# oscillator-v2.net
KiCad netlist of a schematic drawn in EAGLE
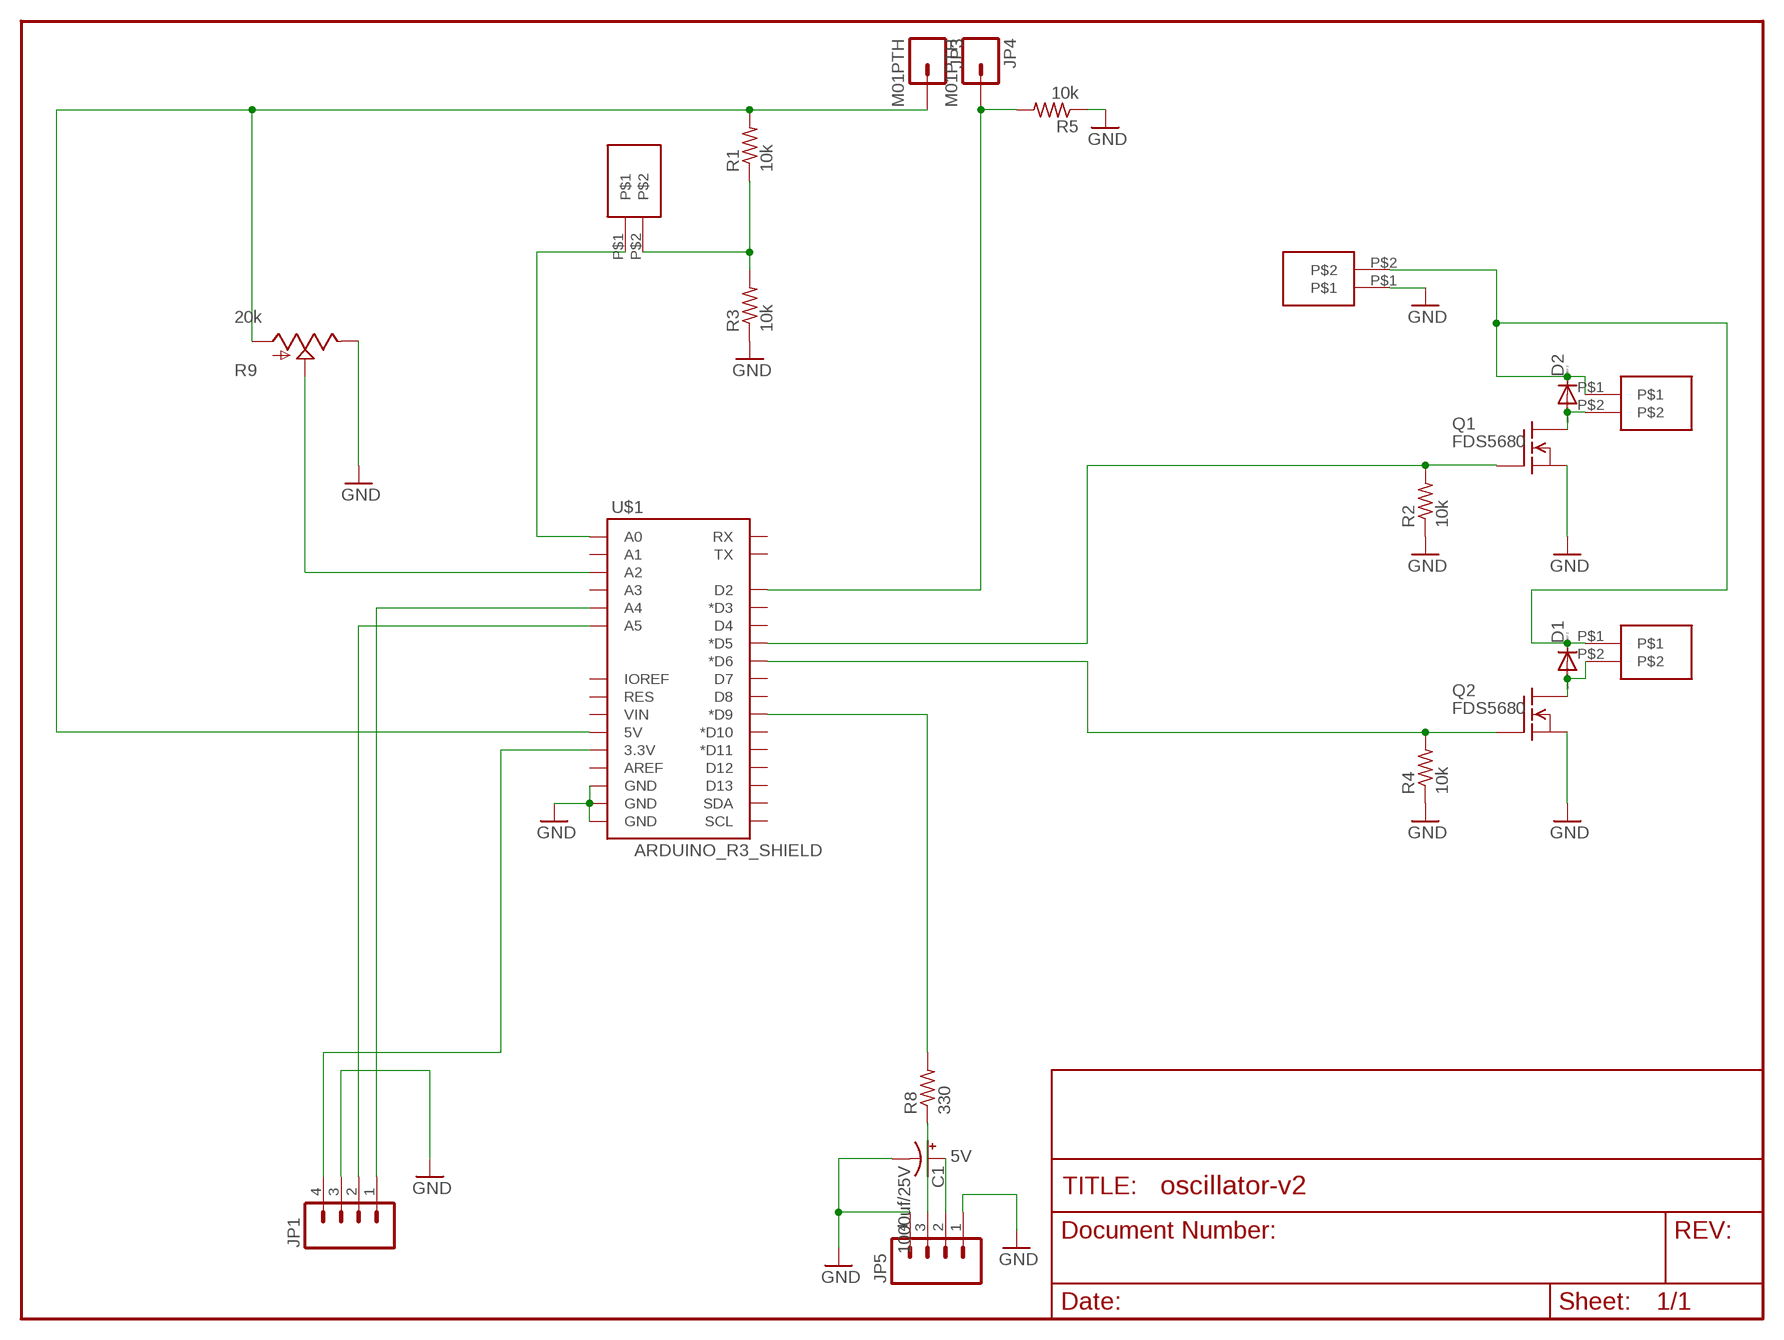
[diagram p0: schematic, sheet 1]

(export (version "E")
  (design (tool "Eeschema 10.0.6"))
  (components
    (comp (ref "C1")
      (value "1000uf/25V")
      (footprint "eagle-import:CPOL-RADIAL-1000UF-25V-KIT")
      (libsource (lib "eagle-import") (part "1000UF-25V(PTH)KIT"))
    )
    (comp (ref "D1")
      (value "DIODE-DO-214AC")
      (footprint "eagle-import:DO-214AC")
      (libsource (lib "eagle-import") (part "DIODE-DO-214AC"))
    )
    (comp (ref "D2")
      (value "DIODE-DO-214AC")
      (footprint "eagle-import:DO-214AC")
      (libsource (lib "eagle-import") (part "DIODE-DO-214AC"))
    )
    (comp (ref "JP1")
      (value "M04PTH")
      (footprint "eagle-import:1X04")
      (libsource (lib "eagle-import") (part "M04PTH"))
    )
    (comp (ref "JP3")
      (value "M01PTH")
      (footprint "eagle-import:1X01")
      (libsource (lib "eagle-import") (part "M01PTH"))
    )
    (comp (ref "JP4")
      (value "M01PTH")
      (footprint "eagle-import:1X01")
      (libsource (lib "eagle-import") (part "M01PTH"))
    )
    (comp (ref "JP5")
      (value "M04PTH")
      (footprint "eagle-import:1X04")
      (libsource (lib "eagle-import") (part "M04PTH"))
    )
    (comp (ref "Q1")
      (value "FDS5680")
      (footprint "eagle-import:SO-8")
      (libsource (lib "eagle-import") (part "FDS5680"))
    )
    (comp (ref "Q2")
      (value "FDS5680")
      (footprint "eagle-import:SO-8")
      (libsource (lib "eagle-import") (part "FDS5680"))
    )
    (comp (ref "R1")
      (value "10k")
      (footprint "eagle-import:R0603")
      (libsource (lib "eagle-import") (part "R-US_R0603"))
    )
    (comp (ref "R2")
      (value "10k")
      (footprint "eagle-import:R0603")
      (libsource (lib "eagle-import") (part "R-US_R0603"))
    )
    (comp (ref "R3")
      (value "10k")
      (footprint "eagle-import:R0603")
      (libsource (lib "eagle-import") (part "R-US_R0603"))
    )
    (comp (ref "R4")
      (value "10k")
      (footprint "eagle-import:R0603")
      (libsource (lib "eagle-import") (part "R-US_R0603"))
    )
    (comp (ref "R5")
      (value "10k")
      (footprint "eagle-import:R0603")
      (libsource (lib "eagle-import") (part "R-US_R0603"))
    )
    (comp (ref "R8")
      (value "330")
      (footprint "eagle-import:R0603")
      (libsource (lib "eagle-import") (part "R-US_R0603"))
    )
    (comp (ref "R9")
      (value "20k")
      (footprint "eagle-import:ALPS_POT_KIT")
      (libsource (lib "eagle-import") (part "POTALPS-KIT"))
    )
    (comp (ref "U$1")
      (value "ARDUINO_R3_SHIELD")
      (footprint "eagle-import:UNO_R3_SHIELD")
      (libsource (lib "eagle-import") (part "ARDUINO_R3_SHIELD"))
    )
    (comp (ref "U$6")
      (value "SPRING-TERMINAL")
      (footprint "eagle-import:SPRING-TERMINAL")
      (libsource (lib "eagle-import") (part "SPRING-TERMINAL"))
    )
    (comp (ref "X1")
      (value "SPRING-TERMINAL")
      (footprint "eagle-import:SPRING-TERMINAL")
      (libsource (lib "eagle-import") (part "SPRING-TERMINAL"))
    )
    (comp (ref "X2")
      (value "SPRING-TERMINAL")
      (footprint "eagle-import:SPRING-TERMINAL")
      (libsource (lib "eagle-import") (part "SPRING-TERMINAL"))
    )
    (comp (ref "X5")
      (value "SPRING-TERMINAL")
      (footprint "eagle-import:SPRING-TERMINAL")
      (libsource (lib "eagle-import") (part "SPRING-TERMINAL"))
    )
  )
  (nets
    (net (code "1") (name "/5V") (class "Default")
      (node (ref "C1") (pin "+") (pinfunction "+_+") (pintype "passive"))
      (node (ref "JP3") (pin "1") (pinfunction "1_1") (pintype "passive"))
      (node (ref "JP5") (pin "2") (pinfunction "2_2") (pintype "passive"))
      (node (ref "R1") (pin "2") (pinfunction "2_2") (pintype "passive"))
      (node (ref "R9") (pin "P$3") (pinfunction "A_P$3") (pintype "passive"))
      (node (ref "U$1") (pin "5V") (pinfunction "5V_5V") (pintype "bidirectional"))
    )
    (net (code "2") (name "GND") (class "Default")
      (node (ref "C1") (pin "-") (pinfunction "-_-") (pintype "passive"))
      (node (ref "JP1") (pin "3") (pinfunction "3_3") (pintype "passive"))
      (node (ref "JP5") (pin "1") (pinfunction "1_1") (pintype "passive"))
      (node (ref "JP5") (pin "4") (pinfunction "4_4") (pintype "passive"))
      (node (ref "Q1") (pin "1") (pinfunction "S_1") (pintype "passive"))
      (node (ref "Q1") (pin "2") (pinfunction "S_2") (pintype "passive"))
      (node (ref "Q1") (pin "3") (pinfunction "S_3") (pintype "passive"))
      (node (ref "Q2") (pin "1") (pinfunction "S_1") (pintype "passive"))
      (node (ref "Q2") (pin "2") (pinfunction "S_2") (pintype "passive"))
      (node (ref "Q2") (pin "3") (pinfunction "S_3") (pintype "passive"))
      (node (ref "R2") (pin "1") (pinfunction "1_1") (pintype "passive"))
      (node (ref "R3") (pin "1") (pinfunction "1_1") (pintype "passive"))
      (node (ref "R4") (pin "1") (pinfunction "1_1") (pintype "passive"))
      (node (ref "R5") (pin "1") (pinfunction "1_1") (pintype "passive"))
      (node (ref "R9") (pin "P$1") (pinfunction "E_P$1") (pintype "passive"))
      (node (ref "U$1") (pin "GND@0") (pinfunction "GND_GND@0") (pintype "bidirectional"))
      (node (ref "U$1") (pin "GND@1") (pinfunction "GND_GND@1") (pintype "bidirectional"))
      (node (ref "U$1") (pin "GND@2") (pinfunction "GND_GND@2") (pintype "bidirectional"))
      (node (ref "X1") (pin "P$1") (pinfunction "P$1_P$1") (pintype "bidirectional"))
    )
    (net (code "3") (name "Net-(D1-PadA)") (class "Default")
      (node (ref "D1") (pin "A") (pinfunction "A_A") (pintype "passive"))
      (node (ref "Q2") (pin "5") (pinfunction "D_5") (pintype "passive"))
      (node (ref "Q2") (pin "6") (pinfunction "D_6") (pintype "passive"))
      (node (ref "Q2") (pin "7") (pinfunction "D_7") (pintype "passive"))
      (node (ref "Q2") (pin "8") (pinfunction "D_8") (pintype "passive"))
      (node (ref "X5") (pin "P$2") (pinfunction "P$2_P$2") (pintype "bidirectional"))
    )
    (net (code "4") (name "Net-(D1-PadC)") (class "Default")
      (node (ref "D1") (pin "C") (pinfunction "C_C") (pintype "passive"))
      (node (ref "D2") (pin "C") (pinfunction "C_C") (pintype "passive"))
      (node (ref "U$6") (pin "P$1") (pinfunction "P$1_P$1") (pintype "bidirectional"))
      (node (ref "X1") (pin "P$2") (pinfunction "P$2_P$2") (pintype "bidirectional"))
      (node (ref "X5") (pin "P$1") (pinfunction "P$1_P$1") (pintype "bidirectional"))
    )
    (net (code "5") (name "Net-(D2-PadA)") (class "Default")
      (node (ref "D2") (pin "A") (pinfunction "A_A") (pintype "passive"))
      (node (ref "Q1") (pin "5") (pinfunction "D_5") (pintype "passive"))
      (node (ref "Q1") (pin "6") (pinfunction "D_6") (pintype "passive"))
      (node (ref "Q1") (pin "7") (pinfunction "D_7") (pintype "passive"))
      (node (ref "Q1") (pin "8") (pinfunction "D_8") (pintype "passive"))
      (node (ref "U$6") (pin "P$2") (pinfunction "P$2_P$2") (pintype "bidirectional"))
    )
    (net (code "6") (name "Net-(JP1-Pad1)") (class "Default")
      (node (ref "JP1") (pin "1") (pinfunction "1_1") (pintype "passive"))
      (node (ref "U$1") (pin "A4") (pinfunction "A4_A4") (pintype "bidirectional"))
    )
    (net (code "7") (name "Net-(JP1-Pad2)") (class "Default")
      (node (ref "JP1") (pin "2") (pinfunction "2_2") (pintype "passive"))
      (node (ref "U$1") (pin "A5") (pinfunction "A5_A5") (pintype "bidirectional"))
    )
    (net (code "8") (name "Net-(JP1-Pad4)") (class "Default")
      (node (ref "JP1") (pin "4") (pinfunction "4_4") (pintype "passive"))
      (node (ref "U$1") (pin "3.3V") (pinfunction "3.3V_3.3V") (pintype "bidirectional"))
    )
    (net (code "9") (name "Net-(JP4-Pad1)") (class "Default")
      (node (ref "JP4") (pin "1") (pinfunction "1_1") (pintype "passive"))
      (node (ref "R5") (pin "2") (pinfunction "2_2") (pintype "passive"))
      (node (ref "U$1") (pin "D2") (pinfunction "D2_D2") (pintype "bidirectional"))
    )
    (net (code "10") (name "Net-(JP5-Pad3)") (class "Default")
      (node (ref "JP5") (pin "3") (pinfunction "3_3") (pintype "passive"))
      (node (ref "R8") (pin "1") (pinfunction "1_1") (pintype "passive"))
    )
    (net (code "11") (name "Net-(Q1-G)") (class "Default")
      (node (ref "Q1") (pin "4") (pinfunction "G_4") (pintype "passive"))
      (node (ref "R2") (pin "2") (pinfunction "2_2") (pintype "passive"))
      (node (ref "U$1") (pin "D5") (pinfunction "*D5_D5") (pintype "bidirectional"))
    )
    (net (code "12") (name "Net-(Q2-G)") (class "Default")
      (node (ref "Q2") (pin "4") (pinfunction "G_4") (pintype "passive"))
      (node (ref "R4") (pin "2") (pinfunction "2_2") (pintype "passive"))
      (node (ref "U$1") (pin "D6") (pinfunction "*D6_D6") (pintype "bidirectional"))
    )
    (net (code "13") (name "Net-(R1-Pad1)") (class "Default")
      (node (ref "R1") (pin "1") (pinfunction "1_1") (pintype "passive"))
      (node (ref "R3") (pin "2") (pinfunction "2_2") (pintype "passive"))
      (node (ref "X2") (pin "P$2") (pinfunction "P$2_P$2") (pintype "bidirectional"))
    )
    (net (code "14") (name "Net-(R9-S)") (class "Default")
      (node (ref "R9") (pin "P$2") (pinfunction "S_P$2") (pintype "passive"))
      (node (ref "U$1") (pin "A2") (pinfunction "A2_A2") (pintype "bidirectional"))
    )
    (net (code "15") (name "Net-(U$1-*D9)") (class "Default")
      (node (ref "R8") (pin "2") (pinfunction "2_2") (pintype "passive"))
      (node (ref "U$1") (pin "D9") (pinfunction "*D9_D9") (pintype "bidirectional"))
    )
    (net (code "16") (name "Net-(U$1-PadA0)") (class "Default")
      (node (ref "U$1") (pin "A0") (pinfunction "A0_A0") (pintype "bidirectional"))
      (node (ref "X2") (pin "P$1") (pinfunction "P$1_P$1") (pintype "bidirectional"))
    )
    (net (code "17") (name "unconnected-(U$1-*D3-PadD3)") (class "Default")
      (node (ref "U$1") (pin "D3") (pinfunction "*D3_D3") (pintype "bidirectional"))
    )
    (net (code "18") (name "unconnected-(U$1-*D10-PadD10)") (class "Default")
      (node (ref "U$1") (pin "D10") (pinfunction "*D10_D10") (pintype "bidirectional"))
    )
    (net (code "19") (name "unconnected-(U$1-*D11-PadD11)") (class "Default")
      (node (ref "U$1") (pin "D11") (pinfunction "*D11_D11") (pintype "bidirectional"))
    )
    (net (code "20") (name "unconnected-(U$1-PadA1)") (class "Default")
      (node (ref "U$1") (pin "A1") (pinfunction "A1_A1") (pintype "bidirectional"))
    )
    (net (code "21") (name "unconnected-(U$1-PadA3)") (class "Default")
      (node (ref "U$1") (pin "A3") (pinfunction "A3_A3") (pintype "bidirectional"))
    )
    (net (code "22") (name "unconnected-(U$1-PadAREF)") (class "Default")
      (node (ref "U$1") (pin "AREF") (pinfunction "AREF_AREF") (pintype "bidirectional"))
    )
    (net (code "23") (name "unconnected-(U$1-PadD4)") (class "Default")
      (node (ref "U$1") (pin "D4") (pinfunction "D4_D4") (pintype "bidirectional"))
    )
    (net (code "24") (name "unconnected-(U$1-PadD7)") (class "Default")
      (node (ref "U$1") (pin "D7") (pinfunction "D7_D7") (pintype "bidirectional"))
    )
    (net (code "25") (name "unconnected-(U$1-PadD8)") (class "Default")
      (node (ref "U$1") (pin "D8") (pinfunction "D8_D8") (pintype "bidirectional"))
    )
    (net (code "26") (name "unconnected-(U$1-PadD12)") (class "Default")
      (node (ref "U$1") (pin "D12") (pinfunction "D12_D12") (pintype "bidirectional"))
    )
    (net (code "27") (name "unconnected-(U$1-PadD13)") (class "Default")
      (node (ref "U$1") (pin "D13") (pinfunction "D13_D13") (pintype "bidirectional"))
    )
    (net (code "28") (name "unconnected-(U$1-PadIOREF)") (class "Default")
      (node (ref "U$1") (pin "IOREF") (pinfunction "IOREF_IOREF") (pintype "bidirectional"))
    )
    (net (code "29") (name "unconnected-(U$1-PadRES)") (class "Default")
      (node (ref "U$1") (pin "RES") (pinfunction "RES_RES") (pintype "bidirectional"))
    )
    (net (code "30") (name "unconnected-(U$1-PadRX)") (class "Default")
      (node (ref "U$1") (pin "RX") (pinfunction "RX_RX") (pintype "bidirectional"))
    )
    (net (code "31") (name "unconnected-(U$1-PadSCL)") (class "Default")
      (node (ref "U$1") (pin "SCL") (pinfunction "SCL_SCL") (pintype "bidirectional"))
    )
    (net (code "32") (name "unconnected-(U$1-PadSDA)") (class "Default")
      (node (ref "U$1") (pin "SDA") (pinfunction "SDA_SDA") (pintype "bidirectional"))
    )
    (net (code "33") (name "unconnected-(U$1-PadTX)") (class "Default")
      (node (ref "U$1") (pin "TX") (pinfunction "TX_TX") (pintype "bidirectional"))
    )
    (net (code "34") (name "unconnected-(U$1-PadVIN)") (class "Default")
      (node (ref "U$1") (pin "VIN") (pinfunction "VIN_VIN") (pintype "bidirectional"))
    )
  )
)
